# powerOneAmp_v2.net
KiCad netlist of a schematic drawn in EAGLE
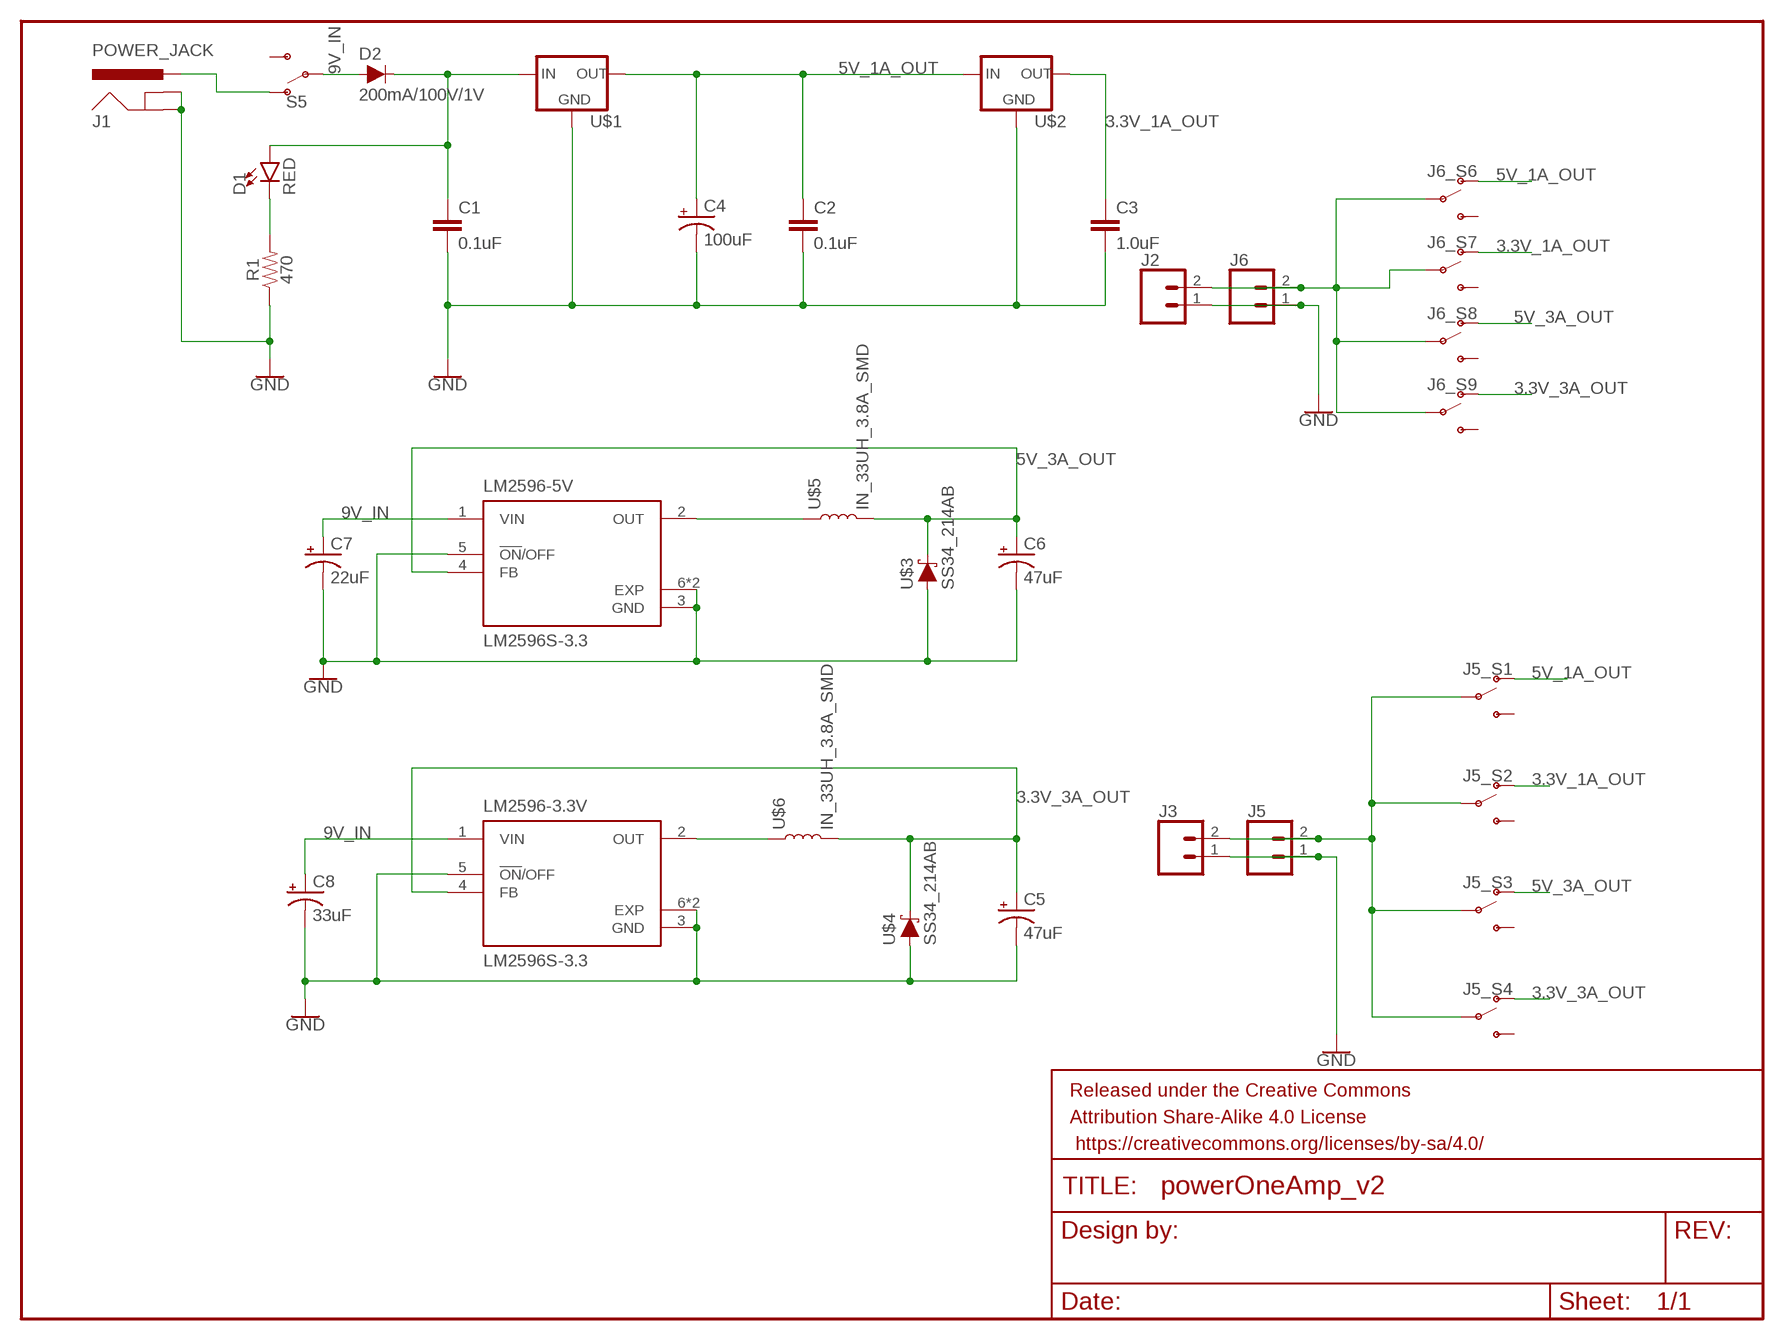
[diagram p0: schematic, sheet 1]

(export (version "E")
  (design (tool "Eeschema 10.0.6"))
  (components
    (comp (ref "C1")
      (value "0.1uF")
      (footprint "eagle-import:0603")
      (libsource (lib "eagle-import") (part "0.1UF-0603-25V-5%"))
    )
    (comp (ref "C2")
      (value "0.1uF")
      (footprint "eagle-import:0603")
      (libsource (lib "eagle-import") (part "0.1UF-0603-25V-5%"))
    )
    (comp (ref "C3")
      (value "1.0uF")
      (footprint "eagle-import:0603")
      (libsource (lib "eagle-import") (part "1.0UF-0603-16V-10%"))
    )
    (comp (ref "C4")
      (value "100uF")
      (footprint "eagle-import:PANASONIC_D")
      (libsource (lib "eagle-import") (part "100UF-POLAR-25V-20%(ELEC)"))
    )
    (comp (ref "C5")
      (value "47uF")
      (footprint "eagle-import:PANASONIC_D")
      (libsource (lib "eagle-import") (part "47UF-POLAR-PANASONIC_D-35V-20%"))
    )
    (comp (ref "C6")
      (value "47uF")
      (footprint "eagle-import:PANASONIC_D")
      (libsource (lib "eagle-import") (part "47UF-POLAR-PANASONIC_D-35V-20%"))
    )
    (comp (ref "C7")
      (value "22uF")
      (footprint "eagle-import:PANASONIC_D")
      (libsource (lib "eagle-import") (part "47UF-POLAR-PANASONIC_D-35V-20%"))
    )
    (comp (ref "C8")
      (value "33uF")
      (footprint "eagle-import:PANASONIC_D")
      (libsource (lib "eagle-import") (part "47UF-POLAR-PANASONIC_D-35V-20%"))
    )
    (comp (ref "D1")
      (value "RED")
      (footprint "eagle-import:LED-0603")
      (libsource (lib "eagle-import") (part "LED-RED0603"))
    )
    (comp (ref "D2")
      (value "200mA/100V/1V")
      (footprint "eagle-import:DIODE-1N4148")
      (libsource (lib "eagle-import") (part "DIODE-1N4148"))
    )
    (comp (ref "FRAME1")
      (value "FRAME-LETTER")
      (footprint "eagle-import:CREATIVE_COMMONS")
      (libsource (lib "eagle-import") (part "FRAME-LETTER"))
    )
    (comp (ref "J1")
      (value "POWER_JACK")
      (footprint "eagle-import:POWER_JACK_PTH")
      (libsource (lib "eagle-import") (part "POWER_JACK"))
    )
    (comp (ref "J2")
      (value "CONN_02")
      (footprint "eagle-import:1X02")
      (libsource (lib "eagle-import") (part "CONN_02"))
    )
    (comp (ref "J3")
      (value "CONN_02")
      (footprint "eagle-import:1X02")
      (libsource (lib "eagle-import") (part "CONN_02"))
    )
    (comp (ref "J5")
      (value "CONN_02")
      (footprint "eagle-import:1X02")
      (libsource (lib "eagle-import") (part "CONN_02"))
    )
    (comp (ref "J5_S1")
      (value "SWITCH-SPDT-PTH-11.6X4.0MM")
      (footprint "eagle-import:SWITCH_SPDT_PTH_11.6X4.0MM")
      (libsource (lib "eagle-import") (part "SWITCH-SPDT-PTH-11.6X4.0MM"))
    )
    (comp (ref "J5_S2")
      (value "SWITCH-SPDT-PTH-11.6X4.0MM")
      (footprint "eagle-import:SWITCH_SPDT_PTH_11.6X4.0MM")
      (libsource (lib "eagle-import") (part "SWITCH-SPDT-PTH-11.6X4.0MM"))
    )
    (comp (ref "J5_S3")
      (value "SWITCH-SPDT-PTH-11.6X4.0MM")
      (footprint "eagle-import:SWITCH_SPDT_PTH_11.6X4.0MM")
      (libsource (lib "eagle-import") (part "SWITCH-SPDT-PTH-11.6X4.0MM"))
    )
    (comp (ref "J5_S4")
      (value "SWITCH-SPDT-PTH-11.6X4.0MM")
      (footprint "eagle-import:SWITCH_SPDT_PTH_11.6X4.0MM")
      (libsource (lib "eagle-import") (part "SWITCH-SPDT-PTH-11.6X4.0MM"))
    )
    (comp (ref "J6")
      (value "CONN_02")
      (footprint "eagle-import:1X02")
      (libsource (lib "eagle-import") (part "CONN_02"))
    )
    (comp (ref "J6_S6")
      (value "SWITCH-SPDT-PTH-11.6X4.0MM")
      (footprint "eagle-import:SWITCH_SPDT_PTH_11.6X4.0MM")
      (libsource (lib "eagle-import") (part "SWITCH-SPDT-PTH-11.6X4.0MM"))
    )
    (comp (ref "J6_S7")
      (value "SWITCH-SPDT-PTH-11.6X4.0MM")
      (footprint "eagle-import:SWITCH_SPDT_PTH_11.6X4.0MM")
      (libsource (lib "eagle-import") (part "SWITCH-SPDT-PTH-11.6X4.0MM"))
    )
    (comp (ref "J6_S8")
      (value "SWITCH-SPDT-PTH-11.6X4.0MM")
      (footprint "eagle-import:SWITCH_SPDT_PTH_11.6X4.0MM")
      (libsource (lib "eagle-import") (part "SWITCH-SPDT-PTH-11.6X4.0MM"))
    )
    (comp (ref "J6_S9")
      (value "SWITCH-SPDT-PTH-11.6X4.0MM")
      (footprint "eagle-import:SWITCH_SPDT_PTH_11.6X4.0MM")
      (libsource (lib "eagle-import") (part "SWITCH-SPDT-PTH-11.6X4.0MM"))
    )
    (comp (ref "LM2596-3.3V")
      (value "LM2596S-3.3")
      (footprint "eagle-import:VREG_LM2596S-3.3")
      (fields (field (name "MF") "Texas Instruments"))
      (libsource (lib "eagle-import") (part "LM2596S-3.3"))
    )
    (comp (ref "LM2596-5V")
      (value "LM2596S-3.3")
      (footprint "eagle-import:VREG_LM2596S-3.3")
      (fields (field (name "MF") "Texas Instruments"))
      (libsource (lib "eagle-import") (part "LM2596S-3.3"))
    )
    (comp (ref "R1")
      (value "470")
      (footprint "eagle-import:0603")
      (libsource (lib "eagle-import") (part "470OHM-0603-1/10W-1%"))
    )
    (comp (ref "S5")
      (value "SWITCH-SPDT-PTH-11.6X4.0MM")
      (footprint "eagle-import:SWITCH_SPDT_PTH_11.6X4.0MM")
      (libsource (lib "eagle-import") (part "SWITCH-SPDT-PTH-11.6X4.0MM"))
    )
    (comp (ref "U$1")
      (value "V_REG_LD1117VXXLD1117-SMD")
      (footprint "eagle-import:SOT223")
      (libsource (lib "eagle-import") (part "V_REG_LD1117VXXLD1117-SMD"))
    )
    (comp (ref "U$2")
      (value "V_REG_LD1117VXXLD1117-SMD")
      (footprint "eagle-import:SOT223")
      (libsource (lib "eagle-import") (part "V_REG_LD1117VXXLD1117-SMD"))
    )
    (comp (ref "U$3")
      (value "SS34_214AB")
      (footprint "eagle-import:SOD-323")
      (libsource (lib "eagle-import") (part "SS34_214AB"))
    )
    (comp (ref "U$4")
      (value "SS34_214AB")
      (footprint "eagle-import:SOD-323")
      (libsource (lib "eagle-import") (part "SS34_214AB"))
    )
    (comp (ref "U$5")
      (value "IN_33UH_3.8A_SMD")
      (footprint "eagle-import:INDUCTOR_4X4MM")
      (libsource (lib "eagle-import") (part "IN_33UH_3.8A_SMD"))
    )
    (comp (ref "U$6")
      (value "IN_33UH_3.8A_SMD")
      (footprint "eagle-import:INDUCTOR_4X4MM")
      (libsource (lib "eagle-import") (part "IN_33UH_3.8A_SMD"))
    )
  )
  (nets
    (net (code "1") (name "/3.3V_1A_OUT") (class "Default")
      (node (ref "C3") (pin "1") (pinfunction "1_1") (pintype "passive"))
      (node (ref "J5_S2") (pin "1") (pinfunction "O_1") (pintype "passive"))
      (node (ref "J6_S7") (pin "1") (pinfunction "O_1") (pintype "passive"))
      (node (ref "U$2") (pin "2") (pinfunction "OUT_2") (pintype "passive"))
    )
    (net (code "2") (name "/3.3V_3A_OUT") (class "Default")
      (node (ref "C5") (pin "+") (pinfunction "+_+") (pintype "passive"))
      (node (ref "J5_S4") (pin "1") (pinfunction "O_1") (pintype "passive"))
      (node (ref "J6_S9") (pin "1") (pinfunction "O_1") (pintype "passive"))
      (node (ref "LM2596-3.3V") (pin "4") (pinfunction "FB_4") (pintype "input"))
      (node (ref "U$4") (pin "C") (pinfunction "C_C") (pintype "passive"))
      (node (ref "U$6") (pin "P$2") (pinfunction "2_P$2") (pintype "passive"))
    )
    (net (code "3") (name "/5V_1A_OUT") (class "Default")
      (node (ref "C2") (pin "1") (pinfunction "1_1") (pintype "passive"))
      (node (ref "C4") (pin "+") (pinfunction "+_+") (pintype "passive"))
      (node (ref "J5_S1") (pin "1") (pinfunction "O_1") (pintype "passive"))
      (node (ref "J6_S6") (pin "1") (pinfunction "O_1") (pintype "passive"))
      (node (ref "U$1") (pin "2") (pinfunction "OUT_2") (pintype "passive"))
      (node (ref "U$2") (pin "3") (pinfunction "IN_3") (pintype "input"))
    )
    (net (code "4") (name "/5V_3A_OUT") (class "Default")
      (node (ref "C6") (pin "+") (pinfunction "+_+") (pintype "passive"))
      (node (ref "J5_S3") (pin "1") (pinfunction "O_1") (pintype "passive"))
      (node (ref "J6_S8") (pin "1") (pinfunction "O_1") (pintype "passive"))
      (node (ref "LM2596-5V") (pin "4") (pinfunction "FB_4") (pintype "input"))
      (node (ref "U$3") (pin "C") (pinfunction "C_C") (pintype "passive"))
      (node (ref "U$5") (pin "P$2") (pinfunction "2_P$2") (pintype "passive"))
    )
    (net (code "5") (name "/9V_IN") (class "Default")
      (node (ref "C7") (pin "+") (pinfunction "+_+") (pintype "passive"))
      (node (ref "C8") (pin "+") (pinfunction "+_+") (pintype "passive"))
      (node (ref "D2") (pin "A") (pinfunction "A_A") (pintype "passive"))
      (node (ref "LM2596-3.3V") (pin "1") (pinfunction "VIN_1") (pintype "input"))
      (node (ref "LM2596-5V") (pin "1") (pinfunction "VIN_1") (pintype "input"))
      (node (ref "S5") (pin "2") (pinfunction "P_2") (pintype "passive"))
    )
    (net (code "6") (name "GND") (class "Default")
      (node (ref "C1") (pin "2") (pinfunction "2_2") (pintype "passive"))
      (node (ref "C2") (pin "2") (pinfunction "2_2") (pintype "passive"))
      (node (ref "C3") (pin "2") (pinfunction "2_2") (pintype "passive"))
      (node (ref "C4") (pin "-") (pinfunction "-_-") (pintype "passive"))
      (node (ref "C5") (pin "-") (pinfunction "-_-") (pintype "passive"))
      (node (ref "C6") (pin "-") (pinfunction "-_-") (pintype "passive"))
      (node (ref "C7") (pin "-") (pinfunction "-_-") (pintype "passive"))
      (node (ref "C8") (pin "-") (pinfunction "-_-") (pintype "passive"))
      (node (ref "J1") (pin "GND") (pinfunction "GND_GND") (pintype "bidirectional"))
      (node (ref "J1") (pin "GNDBREAK") (pinfunction "GNDBREAK_GNDBREAK") (pintype "bidirectional"))
      (node (ref "J2") (pin "1") (pinfunction "1_1") (pintype "passive"))
      (node (ref "J3") (pin "1") (pinfunction "1_1") (pintype "passive"))
      (node (ref "J5") (pin "1") (pinfunction "1_1") (pintype "passive"))
      (node (ref "J6") (pin "1") (pinfunction "1_1") (pintype "passive"))
      (node (ref "LM2596-3.3V") (pin "3") (pinfunction "GND_3") (pintype "power_in"))
      (node (ref "LM2596-3.3V") (pin "5") (pinfunction "~{ON}/OFF_5") (pintype "input"))
      (node (ref "LM2596-3.3V") (pin "6") (pinfunction "EXP_6") (pintype "power_in"))
      (node (ref "LM2596-3.3V") (pin "7") (pinfunction "EXP_7") (pintype "power_in"))
      (node (ref "LM2596-5V") (pin "3") (pinfunction "GND_3") (pintype "power_in"))
      (node (ref "LM2596-5V") (pin "5") (pinfunction "~{ON}/OFF_5") (pintype "input"))
      (node (ref "LM2596-5V") (pin "6") (pinfunction "EXP_6") (pintype "power_in"))
      (node (ref "LM2596-5V") (pin "7") (pinfunction "EXP_7") (pintype "power_in"))
      (node (ref "R1") (pin "1") (pinfunction "1_1") (pintype "passive"))
      (node (ref "U$1") (pin "1") (pinfunction "GND_1") (pintype "input"))
      (node (ref "U$2") (pin "1") (pinfunction "GND_1") (pintype "input"))
      (node (ref "U$3") (pin "A") (pinfunction "A_A") (pintype "passive"))
      (node (ref "U$4") (pin "A") (pinfunction "A_A") (pintype "passive"))
    )
    (net (code "7") (name "Net-(D1-PadC)") (class "Default")
      (node (ref "D1") (pin "C") (pinfunction "C_C") (pintype "passive"))
      (node (ref "R1") (pin "2") (pinfunction "2_2") (pintype "passive"))
    )
    (net (code "8") (name "Net-(J5_S1-P)") (class "Default")
      (node (ref "J3") (pin "2") (pinfunction "2_2") (pintype "passive"))
      (node (ref "J5") (pin "2") (pinfunction "2_2") (pintype "passive"))
      (node (ref "J5_S1") (pin "2") (pinfunction "P_2") (pintype "passive"))
      (node (ref "J5_S2") (pin "2") (pinfunction "P_2") (pintype "passive"))
      (node (ref "J5_S3") (pin "2") (pinfunction "P_2") (pintype "passive"))
      (node (ref "J5_S4") (pin "2") (pinfunction "P_2") (pintype "passive"))
    )
    (net (code "9") (name "Net-(J6_S6-P)") (class "Default")
      (node (ref "J2") (pin "2") (pinfunction "2_2") (pintype "passive"))
      (node (ref "J6") (pin "2") (pinfunction "2_2") (pintype "passive"))
      (node (ref "J6_S6") (pin "2") (pinfunction "P_2") (pintype "passive"))
      (node (ref "J6_S7") (pin "2") (pinfunction "P_2") (pintype "passive"))
      (node (ref "J6_S8") (pin "2") (pinfunction "P_2") (pintype "passive"))
      (node (ref "J6_S9") (pin "2") (pinfunction "P_2") (pintype "passive"))
    )
    (net (code "10") (name "Net-(LM2596-3.3V-OUT)") (class "Default")
      (node (ref "LM2596-3.3V") (pin "2") (pinfunction "OUT_2") (pintype "output"))
      (node (ref "U$6") (pin "P$1") (pinfunction "1_P$1") (pintype "passive"))
    )
    (net (code "11") (name "Net-(LM2596-5V-OUT)") (class "Default")
      (node (ref "LM2596-5V") (pin "2") (pinfunction "OUT_2") (pintype "output"))
      (node (ref "U$5") (pin "P$1") (pinfunction "1_P$1") (pintype "passive"))
    )
    (net (code "12") (name "Net-(S5-O)") (class "Default")
      (node (ref "J1") (pin "PWR") (pinfunction "PWR_PWR") (pintype "bidirectional"))
      (node (ref "S5") (pin "1") (pinfunction "O_1") (pintype "passive"))
    )
    (net (code "13") (name "Net-(U$1-IN)") (class "Default")
      (node (ref "C1") (pin "1") (pinfunction "1_1") (pintype "passive"))
      (node (ref "D1") (pin "A") (pinfunction "A_A") (pintype "passive"))
      (node (ref "D2") (pin "C") (pinfunction "C_C") (pintype "passive"))
      (node (ref "U$1") (pin "3") (pinfunction "IN_3") (pintype "input"))
    )
    (net (code "14") (name "unconnected-(J5_S1-S-Pad3)") (class "Default")
      (node (ref "J5_S1") (pin "3") (pinfunction "S_3") (pintype "passive"))
    )
    (net (code "15") (name "unconnected-(J5_S2-S-Pad3)") (class "Default")
      (node (ref "J5_S2") (pin "3") (pinfunction "S_3") (pintype "passive"))
    )
    (net (code "16") (name "unconnected-(J5_S3-S-Pad3)") (class "Default")
      (node (ref "J5_S3") (pin "3") (pinfunction "S_3") (pintype "passive"))
    )
    (net (code "17") (name "unconnected-(J5_S4-S-Pad3)") (class "Default")
      (node (ref "J5_S4") (pin "3") (pinfunction "S_3") (pintype "passive"))
    )
    (net (code "18") (name "unconnected-(J6_S6-S-Pad3)") (class "Default")
      (node (ref "J6_S6") (pin "3") (pinfunction "S_3") (pintype "passive"))
    )
    (net (code "19") (name "unconnected-(J6_S7-S-Pad3)") (class "Default")
      (node (ref "J6_S7") (pin "3") (pinfunction "S_3") (pintype "passive"))
    )
    (net (code "20") (name "unconnected-(J6_S8-S-Pad3)") (class "Default")
      (node (ref "J6_S8") (pin "3") (pinfunction "S_3") (pintype "passive"))
    )
    (net (code "21") (name "unconnected-(J6_S9-S-Pad3)") (class "Default")
      (node (ref "J6_S9") (pin "3") (pinfunction "S_3") (pintype "passive"))
    )
    (net (code "22") (name "unconnected-(S5-S-Pad3)") (class "Default")
      (node (ref "S5") (pin "3") (pinfunction "S_3") (pintype "passive"))
    )
  )
)
